# 01_Power.net
KiCad netlist of a schematic drawn in Altium Designer
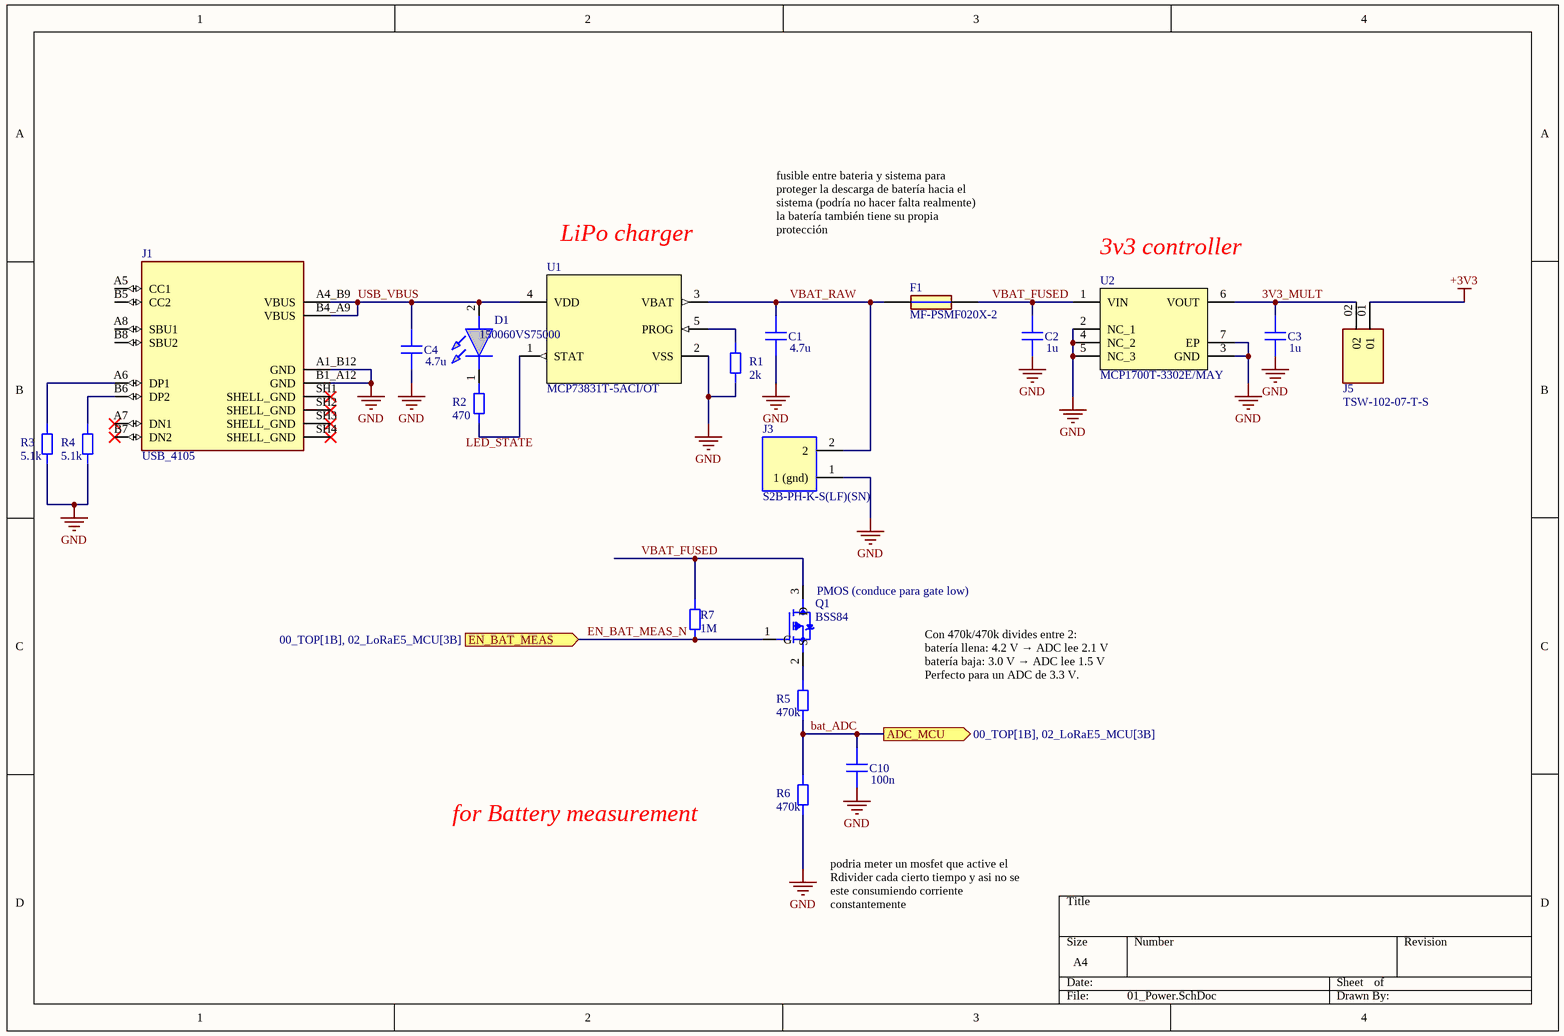
[diagram p0: 01_Power.SchDoc]

(export (version "E")
  (design (tool "Eeschema 10.0.6"))
  (components
    (comp (ref "C1")
      (value "4.7u")
      (footprint "Capacitor_SMD:0603_1608m")
      (libsource (lib "TrashTrack_SCH_LIB") (part "Generic_Capacitor"))
    )
    (comp (ref "C2")
      (value "1u")
      (footprint "Capacitor_SMD:0603_1608m")
      (libsource (lib "TrashTrack_SCH_LIB") (part "Generic_Capacitor"))
    )
    (comp (ref "C3")
      (value "1u")
      (footprint "Capacitor_SMD:0603_1608m")
      (libsource (lib "TrashTrack_SCH_LIB") (part "Generic_Capacitor"))
    )
    (comp (ref "C4")
      (value "4.7u")
      (footprint "Capacitor_SMD:0603_1608m")
      (libsource (lib "TrashTrack_SCH_LIB") (part "Generic_Capacitor"))
    )
    (comp (ref "C10")
      (value "100n")
      (footprint "Capacitor_SMD:0603_1608m")
      (libsource (lib "TrashTrack_SCH_LIB") (part "Generic_Capacitor"))
    )
    (comp (ref "D1")
      (value "150060VS75000")
      (footprint "LEDC1608X70N")
      (fields (field (name "MOUSER PART NUMBER") "710-150060VS75000"))
      (libsource (lib "TrashTrack_SCH_LIB") (part "150060VS75000"))
    )
    (comp (ref "F1")
      (value "MF-PSMF020X-2")
      (footprint "MF-PSMF020X-2")
      (fields (field (name "MOUSER PART NUMBER") "652-MF-PSMF020X-2"))
      (libsource (lib "TrashTrack_SCH_LIB") (part "MF-PSMF020X-2"))
    )
    (comp (ref "J1")
      (value "USB_4105")
      (footprint "USB4105-GF-A")
      (libsource (lib "TrashTrack_SCH_LIB") (part "USB_4105"))
    )
    (comp (ref "J3")
      (value "S2B-PH-K-S(LF)(SN)")
      (footprint "S2B-PH-K-S(LF)(SN)")
      (libsource (lib "TrashTrack_SCH_LIB") (part "S2B-PH-K-S(LF)(SN)"))
    )
    (comp (ref "J5")
      (value "TSW-102-07-T-S")
      (footprint "TSW-102-07-T-S")
      (fields (field (name "MF") "{'manufacturer': u'Samtec'}"))
      (libsource (lib "TrashTrack_SCH_LIB") (part "TSW-102-07-T-S"))
    )
    (comp (ref "Q1")
      (value "BSS84")
      (footprint "BS884")
      (description "P-Channel 50 V 130mA (Ta) 225mW (Ta) Surface Mount SOT-23-3 (TO-236)")
      (fields (field (name "MF") "onsemi"))
      (libsource (lib "TrashTrack_SCH_LIB") (part "BSS84"))
    )
    (comp (ref "R1")
      (value "2k")
      (footprint "Resistor_SMD:0603_1608m")
      (libsource (lib "TrashTrack_SCH_LIB") (part "Generic Resistor"))
    )
    (comp (ref "R2")
      (value "470")
      (footprint "Resistor_SMD:0603_1608m")
      (libsource (lib "TrashTrack_SCH_LIB") (part "Generic Resistor"))
    )
    (comp (ref "R3")
      (value "5.1k")
      (footprint "Resistor_SMD:0603_1608m")
      (libsource (lib "TrashTrack_SCH_LIB") (part "Generic Resistor"))
    )
    (comp (ref "R4")
      (value "5.1k")
      (footprint "Resistor_SMD:0603_1608m")
      (libsource (lib "TrashTrack_SCH_LIB") (part "Generic Resistor"))
    )
    (comp (ref "R5")
      (value "470k")
      (footprint "Resistor_SMD:0603_1608m")
      (libsource (lib "TrashTrack_SCH_LIB") (part "Generic Resistor"))
    )
    (comp (ref "R6")
      (value "470k")
      (footprint "Resistor_SMD:0603_1608m")
      (libsource (lib "TrashTrack_SCH_LIB") (part "Generic Resistor"))
    )
    (comp (ref "R7")
      (value "1M")
      (footprint "Resistor_SMD:0603_1608m")
      (libsource (lib "") (part "Generic Resistor_1"))
    )
    (comp (ref "U1")
      (value "MCP73831T-5ACI/OT")
      (footprint "MCP73831T-5ACI/OT")
      (libsource (lib "TrashTrack_SCH_LIB") (part "MCP73831T-5ACI/OT"))
    )
    (comp (ref "U2")
      (value "MCP1700T-3302E/MAY")
      (footprint "MCP1700T-3302E/MAY")
      (libsource (lib "TrashTrack_SCH_LIB") (part "MCP1700T-3302E/MAY"))
    )
  )
  (nets
    (net (code "1") (name "+3V3") (class "Default")
      (node (ref "J5") (pin "01") (pinfunction "01_01") (pintype "passive"))
    )
    (net (code "2") (name "/3V3_MULT") (class "Default")
      (node (ref "C3") (pin "1") (pintype "passive"))
      (node (ref "J5") (pin "02") (pinfunction "02_02") (pintype "passive"))
      (node (ref "U2") (pin "6") (pinfunction "VOUT_6") (pintype "passive"))
    )
    (net (code "3") (name "/EN_BAT_MEAS_N") (class "Default")
      (node (ref "Q1") (pin "1") (pinfunction "G_1") (pintype "passive"))
      (node (ref "R7") (pin "1") (pintype "passive"))
    )
    (net (code "5") (name "/USB_VBUS") (class "Default")
      (node (ref "C4") (pin "1") (pintype "passive"))
      (node (ref "D1") (pin "2") (pinfunction "A_2") (pintype "passive"))
      (node (ref "J1") (pin "A4_B9") (pinfunction "VBUS_A4_B9") (pintype "power_in"))
      (node (ref "J1") (pin "B4_A9") (pinfunction "VBUS_B4_A9") (pintype "power_in"))
      (node (ref "U1") (pin "4") (pinfunction "VDD_4") (pintype "power_in"))
    )
    (net (code "6") (name "/VBAT_FUSED") (class "Default")
      (node (ref "C2") (pin "1") (pintype "passive"))
      (node (ref "F1") (pin "2") (pinfunction "2_2") (pintype "passive"))
      (node (ref "Q1") (pin "3") (pinfunction "D_3") (pintype "passive"))
      (node (ref "R7") (pin "2") (pintype "passive"))
      (node (ref "U2") (pin "1") (pinfunction "VIN_1") (pintype "passive"))
    )
    (net (code "7") (name "/VBAT_RAW") (class "Default")
      (node (ref "C1") (pin "1") (pintype "passive"))
      (node (ref "F1") (pin "1") (pinfunction "1_1") (pintype "passive"))
      (node (ref "J3") (pin "2") (pinfunction "2_2") (pintype "passive"))
      (node (ref "U1") (pin "3") (pinfunction "VBAT_3") (pintype "output"))
    )
    (net (code "8") (name "/bat_ADC") (class "Default")
      (node (ref "C10") (pin "1") (pintype "passive"))
      (node (ref "R5") (pin "2") (pintype "passive"))
      (node (ref "R6") (pin "1") (pintype "passive"))
    )
    (net (code "9") (name "GND") (class "Default")
      (node (ref "C1") (pin "2") (pintype "passive"))
      (node (ref "C10") (pin "2") (pintype "passive"))
      (node (ref "C2") (pin "2") (pintype "passive"))
      (node (ref "C3") (pin "2") (pintype "passive"))
      (node (ref "C4") (pin "2") (pintype "passive"))
      (node (ref "J1") (pin "A1_B12") (pinfunction "GND_A1_B12") (pintype "power_in"))
      (node (ref "J1") (pin "B1_A12") (pinfunction "GND_B1_A12") (pintype "power_in"))
      (node (ref "J3") (pin "1") (pinfunction "1_(gnd)_1") (pintype "passive"))
      (node (ref "R1") (pin "2") (pintype "passive"))
      (node (ref "R3") (pin "2") (pintype "passive"))
      (node (ref "R4") (pin "2") (pintype "passive"))
      (node (ref "R6") (pin "2") (pintype "passive"))
      (node (ref "U1") (pin "2") (pinfunction "VSS_2") (pintype "power_in"))
      (node (ref "U2") (pin "2") (pinfunction "NC_1_2") (pintype "passive"))
      (node (ref "U2") (pin "3") (pinfunction "GND_3") (pintype "passive"))
      (node (ref "U2") (pin "4") (pinfunction "NC_2_4") (pintype "passive"))
      (node (ref "U2") (pin "5") (pinfunction "NC_3_5") (pintype "passive"))
      (node (ref "U2") (pin "7") (pinfunction "EP_7") (pintype "passive"))
    )
    (net (code "10") (name "Net-(D1-K)") (class "Default")
      (node (ref "D1") (pin "1") (pinfunction "K_1") (pintype "passive"))
      (node (ref "R2") (pin "1") (pintype "passive"))
    )
    (net (code "11") (name "Net-(J1-DP1)") (class "Default")
      (node (ref "J1") (pin "A6") (pinfunction "DP1_A6") (pintype "bidirectional"))
      (node (ref "R3") (pin "1") (pintype "passive"))
    )
    (net (code "12") (name "Net-(J1-DP2)") (class "Default")
      (node (ref "J1") (pin "B6") (pinfunction "DP2_B6") (pintype "bidirectional"))
      (node (ref "R4") (pin "1") (pintype "passive"))
    )
    (net (code "13") (name "Net-(Q1-S)") (class "Default")
      (node (ref "Q1") (pin "2") (pinfunction "S_2") (pintype "passive"))
      (node (ref "R5") (pin "1") (pintype "passive"))
    )
    (net (code "14") (name "Net-(U1-PROG)") (class "Default")
      (node (ref "R1") (pin "1") (pintype "passive"))
      (node (ref "U1") (pin "5") (pinfunction "PROG_5") (pintype "input"))
    )
    (net (code "15") (name "Net-(U1-STAT)") (class "Default")
      (node (ref "R2") (pin "2") (pintype "passive"))
      (node (ref "U1") (pin "1") (pinfunction "STAT_1") (pintype "output"))
    )
    (net (code "16") (name "unconnected-(J1-CC1-PadA5)") (class "Default")
      (node (ref "J1") (pin "A5") (pinfunction "CC1_A5") (pintype "bidirectional"))
    )
    (net (code "17") (name "unconnected-(J1-CC2-PadB5)") (class "Default")
      (node (ref "J1") (pin "B5") (pinfunction "CC2_B5") (pintype "bidirectional"))
    )
    (net (code "18") (name "unconnected-(J1-DN1-PadA7)") (class "Default")
      (node (ref "J1") (pin "A7") (pinfunction "DN1_A7") (pintype "bidirectional+no_connect"))
    )
    (net (code "19") (name "unconnected-(J1-DN2-PadB7)") (class "Default")
      (node (ref "J1") (pin "B7") (pinfunction "DN2_B7") (pintype "bidirectional+no_connect"))
    )
    (net (code "20") (name "unconnected-(J1-SBU1-PadA8)") (class "Default")
      (node (ref "J1") (pin "A8") (pinfunction "SBU1_A8") (pintype "bidirectional"))
    )
    (net (code "21") (name "unconnected-(J1-SBU2-PadB8)") (class "Default")
      (node (ref "J1") (pin "B8") (pinfunction "SBU2_B8") (pintype "bidirectional"))
    )
    (net (code "22") (name "unconnected-(J1-SHELL_GND-PadSH1)") (class "Default")
      (node (ref "J1") (pin "SH1") (pinfunction "SHELL_GND_SH1") (pintype "power_in+no_connect"))
    )
    (net (code "23") (name "unconnected-(J1-SHELL_GND-PadSH2)") (class "Default")
      (node (ref "J1") (pin "SH2") (pinfunction "SHELL_GND_SH2") (pintype "power_in+no_connect"))
    )
    (net (code "24") (name "unconnected-(J1-SHELL_GND-PadSH3)") (class "Default")
      (node (ref "J1") (pin "SH3") (pinfunction "SHELL_GND_SH3") (pintype "power_in+no_connect"))
    )
    (net (code "25") (name "unconnected-(J1-SHELL_GND-PadSH4)") (class "Default")
      (node (ref "J1") (pin "SH4") (pinfunction "SHELL_GND_SH4") (pintype "power_in+no_connect"))
    )
  )
)
